# train.net
KiCad netlist of a schematic drawn in EAGLE
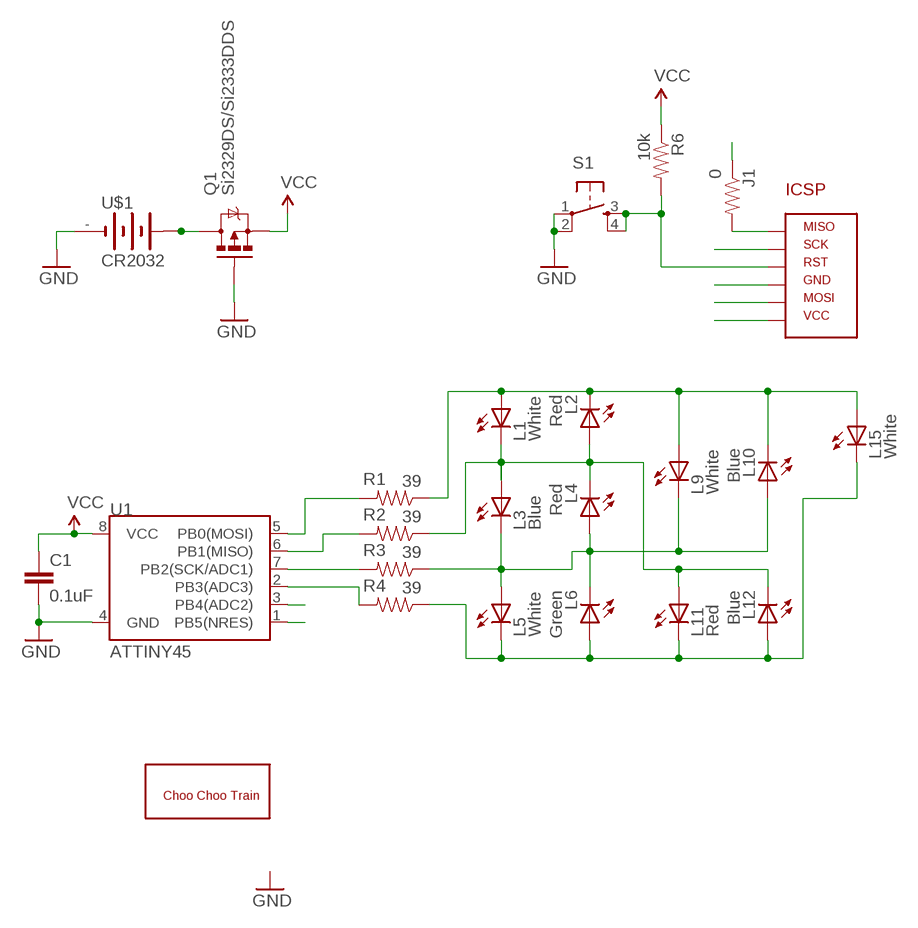
[diagram p0: schematic, sheet 1]

(export (version "E")
  (design (tool "Eeschema 10.0.6"))
  (components
    (comp (ref "C1")
      (value "0.1uF")
      (footprint "eagle-import:0805")
      (libsource (lib "eagle-import") (part "CAP0805"))
    )
    (comp (ref "J1")
      (value "0")
      (footprint "eagle-import:0805")
      (libsource (lib "eagle-import") (part "RESISTOR0805-RES"))
    )
    (comp (ref "L1")
      (value "White")
      (footprint "eagle-import:LED-0805-RED")
      (libsource (lib "eagle-import") (part "LED0805-RED"))
    )
    (comp (ref "L2")
      (value "Red")
      (footprint "eagle-import:LED-0805-RED")
      (libsource (lib "eagle-import") (part "LED0805-RED"))
    )
    (comp (ref "L3")
      (value "Blue")
      (footprint "eagle-import:LED-0805-RED")
      (libsource (lib "eagle-import") (part "LED0805-RED"))
    )
    (comp (ref "L4")
      (value "Red")
      (footprint "eagle-import:LED-0805-RED")
      (libsource (lib "eagle-import") (part "LED0805-RED"))
    )
    (comp (ref "L5")
      (value "White")
      (footprint "eagle-import:LED-0805-RED")
      (libsource (lib "eagle-import") (part "LED0805-RED"))
    )
    (comp (ref "L6")
      (value "Green")
      (footprint "eagle-import:LED-0805-BLUE")
      (libsource (lib "eagle-import") (part "LED0805-BLUE"))
    )
    (comp (ref "L9")
      (value "White")
      (footprint "eagle-import:LED-0805-YELLOW")
      (libsource (lib "eagle-import") (part "LED0805-YELLOW"))
    )
    (comp (ref "L10")
      (value "Blue")
      (footprint "eagle-import:LED-0805-BLUE")
      (libsource (lib "eagle-import") (part "LED0805-BLUE"))
    )
    (comp (ref "L11")
      (value "Red")
      (footprint "eagle-import:LED-0805-BLUE")
      (libsource (lib "eagle-import") (part "LED0805-BLUE"))
    )
    (comp (ref "L12")
      (value "Blue")
      (footprint "eagle-import:LED-0805-RED")
      (libsource (lib "eagle-import") (part "LED0805-RED"))
    )
    (comp (ref "L15")
      (value "White")
      (footprint "eagle-import:LED-0805-BLUE")
      (libsource (lib "eagle-import") (part "LED0805-BLUE"))
    )
    (comp (ref "Q1")
      (value "Si2329DS/Si2333DDS")
      (footprint "eagle-import:SOT23-3")
      (libsource (lib "eagle-import") (part "MOSFET_P_CH"))
    )
    (comp (ref "R1")
      (value "39")
      (footprint "eagle-import:0805")
      (libsource (lib "eagle-import") (part "SparkFun-Resistors_RESISTOR0805-RES"))
    )
    (comp (ref "R2")
      (value "39")
      (footprint "eagle-import:0805")
      (libsource (lib "eagle-import") (part "SparkFun-Resistors_RESISTOR0805-RES"))
    )
    (comp (ref "R3")
      (value "39")
      (footprint "eagle-import:0805")
      (libsource (lib "eagle-import") (part "SparkFun-Resistors_RESISTOR0805-RES"))
    )
    (comp (ref "R4")
      (value "39")
      (footprint "eagle-import:0805")
      (libsource (lib "eagle-import") (part "SparkFun-Resistors_RESISTOR0805-RES"))
    )
    (comp (ref "R6")
      (value "10k")
      (footprint "eagle-import:0805")
      (libsource (lib "eagle-import") (part "SparkFun-Resistors_RESISTOR0805-RES"))
    )
    (comp (ref "S1")
      (value "TAC_SWITCHSMD")
      (footprint "eagle-import:TACTILE_SWITCH_SMD")
      (libsource (lib "eagle-import") (part "TAC_SWITCHSMD"))
    )
    (comp (ref "U$1")
      (value "CR2032")
      (footprint "eagle-import:BAT-HLD-001")
      (libsource (lib "eagle-import") (part "BAT-HLD-001"))
    )
    (comp (ref "U$2")
      (value "AVR_ICSP_6P1X6")
      (footprint "eagle-import:AVR_ICSP_1X6_SMD")
      (libsource (lib "eagle-import") (part "AVR_ICSP_6P1X6"))
    )
    (comp (ref "U$3")
      (value "5X6_CHOOCHOOTRAIN")
      (footprint "eagle-import:CHOOCHOO")
      (libsource (lib "eagle-import") (part "5X6_CHOOCHOOTRAIN"))
    )
    (comp (ref "U1")
      (value "ATTINY45")
      (footprint "eagle-import:SO08-EIAJ")
      (libsource (lib "eagle-import") (part "ATTINY45"))
    )
  )
  (nets
    (net (code "1") (name "/MISO") (class "Default")
      (node (ref "J1") (pin "1") (pinfunction "1_1") (pintype "passive"))
      (node (ref "R2") (pin "2") (pinfunction "2_2") (pintype "passive"))
      (node (ref "U1") (pin "6") (pinfunction "PB1(MISO)_6") (pintype "bidirectional"))
    )
    (net (code "2") (name "/MOSI") (class "Default")
      (node (ref "R1") (pin "2") (pinfunction "2_2") (pintype "passive"))
      (node (ref "U$2") (pin "P4") (pinfunction "MOSI_P4") (pintype "bidirectional"))
      (node (ref "U1") (pin "5") (pinfunction "PB0(MOSI)_5") (pintype "bidirectional"))
    )
    (net (code "3") (name "/RST") (class "Default")
      (node (ref "R6") (pin "2") (pinfunction "2_2") (pintype "passive"))
      (node (ref "S1") (pin "3") (pinfunction "3_3") (pintype "passive"))
      (node (ref "S1") (pin "4") (pinfunction "4_4") (pintype "passive"))
      (node (ref "U$2") (pin "P3") (pinfunction "RST_P3") (pintype "bidirectional"))
      (node (ref "U1") (pin "1") (pinfunction "PB5(NRES)_1") (pintype "bidirectional"))
    )
    (net (code "4") (name "/SCK") (class "Default")
      (node (ref "R3") (pin "2") (pinfunction "2_2") (pintype "passive"))
      (node (ref "U$2") (pin "P2") (pinfunction "SCK_P2") (pintype "bidirectional"))
      (node (ref "U1") (pin "7") (pinfunction "PB2(SCK/ADC1)_7") (pintype "bidirectional"))
    )
    (net (code "5") (name "GND") (class "Default")
      (node (ref "C1") (pin "2") (pinfunction "2_2") (pintype "passive"))
      (node (ref "Q1") (pin "1") (pinfunction "G_1") (pintype "passive"))
      (node (ref "S1") (pin "1") (pinfunction "1_1") (pintype "passive"))
      (node (ref "S1") (pin "2") (pinfunction "2_2") (pintype "passive"))
      (node (ref "U$1") (pin "-") (pinfunction "-_-") (pintype "passive"))
      (node (ref "U$2") (pin "P6") (pinfunction "GND_P6") (pintype "bidirectional"))
      (node (ref "U1") (pin "4") (pinfunction "GND_4") (pintype "bidirectional"))
    )
    (net (code "6") (name "Net-(L1-PadA)") (class "Default")
      (node (ref "L1") (pin "A") (pinfunction "A_A") (pintype "passive"))
      (node (ref "L10") (pin "C") (pinfunction "C_C") (pintype "passive"))
      (node (ref "L15") (pin "A") (pinfunction "A_A") (pintype "passive"))
      (node (ref "L2") (pin "C") (pinfunction "C_C") (pintype "passive"))
      (node (ref "L9") (pin "A") (pinfunction "A_A") (pintype "passive"))
      (node (ref "R1") (pin "1") (pinfunction "1_1") (pintype "passive"))
    )
    (net (code "7") (name "Net-(L1-PadC)") (class "Default")
      (node (ref "L1") (pin "C") (pinfunction "C_C") (pintype "passive"))
      (node (ref "L11") (pin "A") (pinfunction "A_A") (pintype "passive"))
      (node (ref "L12") (pin "C") (pinfunction "C_C") (pintype "passive"))
      (node (ref "L2") (pin "A") (pinfunction "A_A") (pintype "passive"))
      (node (ref "L3") (pin "A") (pinfunction "A_A") (pintype "passive"))
      (node (ref "L4") (pin "C") (pinfunction "C_C") (pintype "passive"))
      (node (ref "R2") (pin "1") (pinfunction "1_1") (pintype "passive"))
    )
    (net (code "8") (name "Net-(L10-PadA)") (class "Default")
      (node (ref "L10") (pin "A") (pinfunction "A_A") (pintype "passive"))
      (node (ref "L3") (pin "C") (pinfunction "C_C") (pintype "passive"))
      (node (ref "L4") (pin "A") (pinfunction "A_A") (pintype "passive"))
      (node (ref "L5") (pin "A") (pinfunction "A_A") (pintype "passive"))
      (node (ref "L6") (pin "C") (pinfunction "C_C") (pintype "passive"))
      (node (ref "L9") (pin "C") (pinfunction "C_C") (pintype "passive"))
      (node (ref "R3") (pin "1") (pinfunction "1_1") (pintype "passive"))
    )
    (net (code "9") (name "Net-(L11-PadC)") (class "Default")
      (node (ref "L11") (pin "C") (pinfunction "C_C") (pintype "passive"))
      (node (ref "L12") (pin "A") (pinfunction "A_A") (pintype "passive"))
      (node (ref "L15") (pin "C") (pinfunction "C_C") (pintype "passive"))
      (node (ref "L5") (pin "C") (pinfunction "C_C") (pintype "passive"))
      (node (ref "L6") (pin "A") (pinfunction "A_A") (pintype "passive"))
      (node (ref "R4") (pin "1") (pinfunction "1_1") (pintype "passive"))
    )
    (net (code "10") (name "Net-(Q1-D)") (class "Default")
      (node (ref "Q1") (pin "3") (pinfunction "D_3") (pintype "passive"))
      (node (ref "U$1") (pin "+@1") (pinfunction "+_+@1") (pintype "passive"))
      (node (ref "U$1") (pin "+@2") (pinfunction "+_+@2") (pintype "passive"))
    )
    (net (code "11") (name "Net-(U$2-MISO)") (class "Default")
      (node (ref "J1") (pin "2") (pinfunction "2_2") (pintype "passive"))
      (node (ref "U$2") (pin "P5") (pinfunction "MISO_P5") (pintype "bidirectional"))
    )
    (net (code "12") (name "Net-(U1-PB3(ADC3))") (class "Default")
      (node (ref "R4") (pin "2") (pinfunction "2_2") (pintype "passive"))
      (node (ref "U1") (pin "2") (pinfunction "PB3(ADC3)_2") (pintype "bidirectional"))
    )
    (net (code "13") (name "VCC") (class "Default")
      (node (ref "C1") (pin "1") (pinfunction "1_1") (pintype "passive"))
      (node (ref "Q1") (pin "2") (pinfunction "S_2") (pintype "passive"))
      (node (ref "R6") (pin "1") (pinfunction "1_1") (pintype "passive"))
      (node (ref "U$2") (pin "P1") (pinfunction "VCC_P1") (pintype "bidirectional"))
      (node (ref "U1") (pin "8") (pinfunction "VCC_8") (pintype "bidirectional"))
    )
    (net (code "14") (name "unconnected-(U1-PB4(ADC2)-Pad3)") (class "Default")
      (node (ref "U1") (pin "3") (pinfunction "PB4(ADC2)_3") (pintype "bidirectional"))
    )
  )
)
